# q3.net
KiCad netlist of a schematic drawn in EAGLE
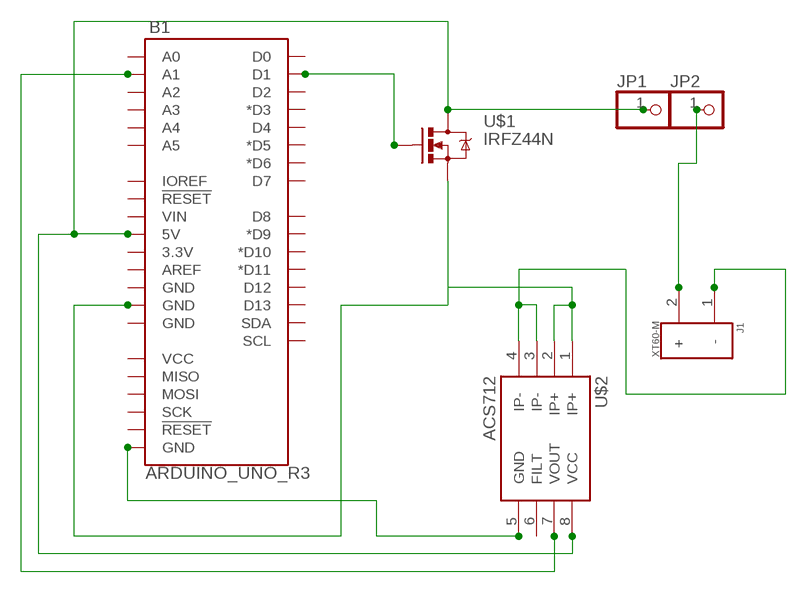
[diagram p0: schematic, sheet 1]

(export (version "E")
  (design (tool "Eeschema 10.0.6"))
  (components
    (comp (ref "B1")
      (value "ARDUINO_UNO_R3")
      (footprint "eagle-import:ARDUINO_R3")
      (libsource (lib "eagle-import") (part "ARDUINO_UNO_R3"))
    )
    (comp (ref "J1")
      (value "XT60-M")
      (footprint "eagle-import:AMASS_XT60-M")
      (fields (field (name "MF") "AMASS"))
      (libsource (lib "eagle-import") (part "XT60-M"))
    )
    (comp (ref "JP1")
      (value "PINHD-1X1")
      (footprint "eagle-import:1X01")
      (libsource (lib "eagle-import") (part "PINHD-1X1"))
    )
    (comp (ref "JP2")
      (value "PINHD-1X1")
      (footprint "eagle-import:1X01")
      (libsource (lib "eagle-import") (part "PINHD-1X1"))
    )
    (comp (ref "U$1")
      (value "IRFZ44N")
      (footprint "eagle-import:TO-220")
      (fields (field (name "MF") "Infineon Technologies"))
      (libsource (lib "eagle-import") (part "IRFZ44N"))
    )
    (comp (ref "U$2")
      (value "ACS712")
      (footprint "eagle-import:SO08")
      (libsource (lib "eagle-import") (part "ACS712"))
    )
  )
  (nets
    (net (code "1") (name "Net-(J1-+)") (class "Default")
      (node (ref "J1") (pin "2") (pinfunction "+_2") (pintype "passive"))
      (node (ref "JP2") (pin "1") (pinfunction "1_1") (pintype "passive"))
    )
    (net (code "2") (name "Net-(J1--)") (class "Default")
      (node (ref "J1") (pin "1") (pinfunction "-_1") (pintype "passive"))
      (node (ref "U$2") (pin "3") (pinfunction "IP-_3") (pintype "bidirectional"))
      (node (ref "U$2") (pin "4") (pinfunction "IP-_4") (pintype "bidirectional"))
    )
    (net (code "3") (name "Net-(U$1-D)") (class "Default")
      (node (ref "B1") (pin "5V") (pinfunction "5V_5V") (pintype "bidirectional"))
      (node (ref "JP1") (pin "1") (pinfunction "1_1") (pintype "passive"))
      (node (ref "U$1") (pin "2") (pinfunction "D_2") (pintype "passive"))
      (node (ref "U$2") (pin "8") (pinfunction "VCC_8") (pintype "bidirectional"))
    )
    (net (code "4") (name "Net-(U$1-G)") (class "Default")
      (node (ref "B1") (pin "D1") (pinfunction "D1_D1") (pintype "bidirectional"))
      (node (ref "U$1") (pin "1") (pinfunction "G_1") (pintype "passive"))
    )
    (net (code "5") (name "Net-(U$1-S)") (class "Default")
      (node (ref "B1") (pin "GND@3") (pinfunction "GND_GND@3") (pintype "bidirectional"))
      (node (ref "U$1") (pin "3") (pinfunction "S_3") (pintype "passive"))
      (node (ref "U$2") (pin "1") (pinfunction "IP+_1") (pintype "bidirectional"))
      (node (ref "U$2") (pin "2") (pinfunction "IP+_2") (pintype "bidirectional"))
    )
    (net (code "6") (name "Net-(U$2-GND)") (class "Default")
      (node (ref "B1") (pin "GND@1") (pinfunction "GND_GND@1") (pintype "bidirectional"))
      (node (ref "U$2") (pin "5") (pinfunction "GND_5") (pintype "bidirectional"))
    )
    (net (code "7") (name "Net-(U$2-VOUT)") (class "Default")
      (node (ref "B1") (pin "A1") (pinfunction "A1_A1") (pintype "bidirectional"))
      (node (ref "U$2") (pin "7") (pinfunction "VOUT_7") (pintype "bidirectional"))
    )
    (net (code "8") (name "unconnected-(B1-*D3-PadD3)") (class "Default")
      (node (ref "B1") (pin "D3") (pinfunction "*D3_D3") (pintype "bidirectional"))
    )
    (net (code "9") (name "unconnected-(B1-*D5-PadD5)") (class "Default")
      (node (ref "B1") (pin "D5") (pinfunction "*D5_D5") (pintype "bidirectional"))
    )
    (net (code "10") (name "unconnected-(B1-*D6-PadD6)") (class "Default")
      (node (ref "B1") (pin "D6") (pinfunction "*D6_D6") (pintype "bidirectional"))
    )
    (net (code "11") (name "unconnected-(B1-*D9-PadD9)") (class "Default")
      (node (ref "B1") (pin "D9") (pinfunction "*D9_D9") (pintype "bidirectional"))
    )
    (net (code "12") (name "unconnected-(B1-*D10-PadD10)") (class "Default")
      (node (ref "B1") (pin "D10") (pinfunction "*D10_D10") (pintype "bidirectional"))
    )
    (net (code "13") (name "unconnected-(B1-*D11-PadD11)") (class "Default")
      (node (ref "B1") (pin "D11") (pinfunction "*D11_D11") (pintype "bidirectional"))
    )
    (net (code "14") (name "unconnected-(B1-GND-PadGND@2)") (class "Default")
      (node (ref "B1") (pin "GND@2") (pinfunction "GND_GND@2") (pintype "bidirectional"))
    )
    (net (code "15") (name "unconnected-(B1-GND-PadGND@4)") (class "Default")
      (node (ref "B1") (pin "GND@4") (pinfunction "GND_GND@4") (pintype "bidirectional"))
    )
    (net (code "16") (name "unconnected-(B1-Pad3.3V)") (class "Default")
      (node (ref "B1") (pin "3.3V") (pinfunction "3.3V_3.3V") (pintype "bidirectional"))
    )
    (net (code "17") (name "unconnected-(B1-PadA0)") (class "Default")
      (node (ref "B1") (pin "A0") (pinfunction "A0_A0") (pintype "bidirectional"))
    )
    (net (code "18") (name "unconnected-(B1-PadA2)") (class "Default")
      (node (ref "B1") (pin "A2") (pinfunction "A2_A2") (pintype "bidirectional"))
    )
    (net (code "19") (name "unconnected-(B1-PadA3)") (class "Default")
      (node (ref "B1") (pin "A3") (pinfunction "A3_A3") (pintype "bidirectional"))
    )
    (net (code "20") (name "unconnected-(B1-PadA4)") (class "Default")
      (node (ref "B1") (pin "A4") (pinfunction "A4_A4") (pintype "bidirectional"))
    )
    (net (code "21") (name "unconnected-(B1-PadA5)") (class "Default")
      (node (ref "B1") (pin "A5") (pinfunction "A5_A5") (pintype "bidirectional"))
    )
    (net (code "22") (name "unconnected-(B1-PadAREF)") (class "Default")
      (node (ref "B1") (pin "AREF") (pinfunction "AREF_AREF") (pintype "bidirectional"))
    )
    (net (code "23") (name "unconnected-(B1-PadD0)") (class "Default")
      (node (ref "B1") (pin "D0") (pinfunction "D0_D0") (pintype "bidirectional"))
    )
    (net (code "24") (name "unconnected-(B1-PadD2)") (class "Default")
      (node (ref "B1") (pin "D2") (pinfunction "D2_D2") (pintype "bidirectional"))
    )
    (net (code "25") (name "unconnected-(B1-PadD4)") (class "Default")
      (node (ref "B1") (pin "D4") (pinfunction "D4_D4") (pintype "bidirectional"))
    )
    (net (code "26") (name "unconnected-(B1-PadD7)") (class "Default")
      (node (ref "B1") (pin "D7") (pinfunction "D7_D7") (pintype "bidirectional"))
    )
    (net (code "27") (name "unconnected-(B1-PadD8)") (class "Default")
      (node (ref "B1") (pin "D8") (pinfunction "D8_D8") (pintype "bidirectional"))
    )
    (net (code "28") (name "unconnected-(B1-PadD12)") (class "Default")
      (node (ref "B1") (pin "D12") (pinfunction "D12_D12") (pintype "bidirectional"))
    )
    (net (code "29") (name "unconnected-(B1-PadD13)") (class "Default")
      (node (ref "B1") (pin "D13") (pinfunction "D13_D13") (pintype "bidirectional"))
    )
    (net (code "30") (name "unconnected-(B1-PadIOREF)") (class "Default")
      (node (ref "B1") (pin "IOREF") (pinfunction "IOREF_IOREF") (pintype "bidirectional"))
    )
    (net (code "31") (name "unconnected-(B1-PadMISO)") (class "Default")
      (node (ref "B1") (pin "MISO") (pinfunction "MISO_MISO") (pintype "bidirectional"))
    )
    (net (code "32") (name "unconnected-(B1-PadMOSI)") (class "Default")
      (node (ref "B1") (pin "MOSI") (pinfunction "MOSI_MOSI") (pintype "bidirectional"))
    )
    (net (code "33") (name "unconnected-(B1-PadSCK)") (class "Default")
      (node (ref "B1") (pin "SCK") (pinfunction "SCK_SCK") (pintype "bidirectional"))
    )
    (net (code "34") (name "unconnected-(B1-PadSCL)") (class "Default")
      (node (ref "B1") (pin "SCL") (pinfunction "SCL_SCL") (pintype "bidirectional"))
    )
    (net (code "35") (name "unconnected-(B1-PadSDA)") (class "Default")
      (node (ref "B1") (pin "SDA") (pinfunction "SDA_SDA") (pintype "bidirectional"))
    )
    (net (code "36") (name "unconnected-(B1-PadVCC)") (class "Default")
      (node (ref "B1") (pin "VCC") (pinfunction "VCC_VCC") (pintype "bidirectional"))
    )
    (net (code "37") (name "unconnected-(B1-PadVIN)") (class "Default")
      (node (ref "B1") (pin "VIN") (pinfunction "VIN_VIN") (pintype "bidirectional"))
    )
    (net (code "38") (name "unconnected-(B1-~{RESET}-PadRESET@1)") (class "Default")
      (node (ref "B1") (pin "RESET@1") (pinfunction "~{RESET}_RESET@1") (pintype "bidirectional"))
    )
    (net (code "39") (name "unconnected-(B1-~{RESET}-PadRESET@2)") (class "Default")
      (node (ref "B1") (pin "RESET@2") (pinfunction "~{RESET}_RESET@2") (pintype "bidirectional"))
    )
    (net (code "40") (name "unconnected-(U$2-FILT-Pad6)") (class "Default")
      (node (ref "U$2") (pin "6") (pinfunction "FILT_6") (pintype "bidirectional"))
    )
  )
)
